# joint_board_boosterpack_hall_effect_enco.net
KiCad netlist of a schematic drawn in Altium Designer
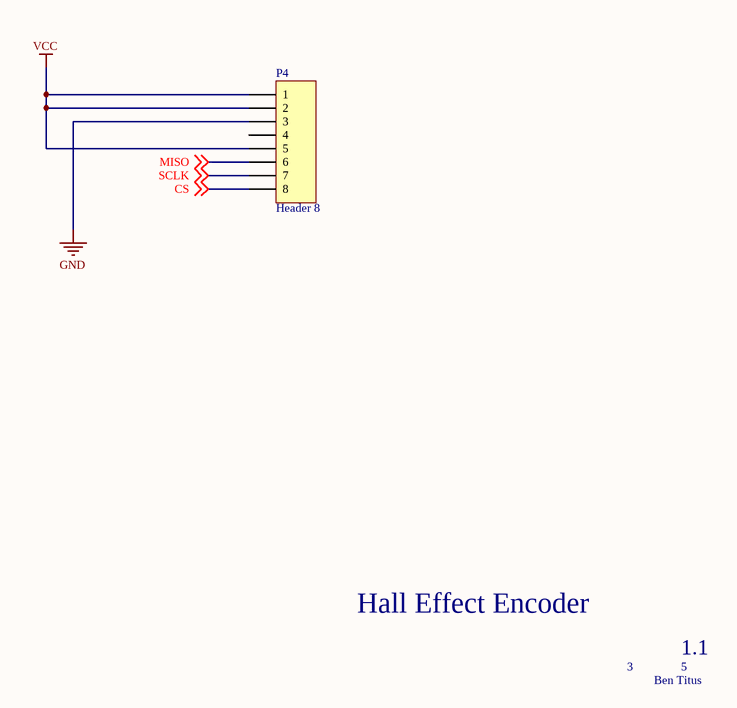
[diagram p0: joint_board_boosterpack_hall_effect_encoder.SchDoc]

(export (version "E")
  (design (tool "Eeschema 10.0.6"))
  (components
    (comp (ref "P4")
      (value "Header 8")
      (footprint "HDR1X8")
      (description "Header, 8-Pin")
      (fields (field (name "PUBLISHER") "Altium Limited"))
      (libsource (lib "Miscellaneous Connectors") (part "Header 8"))
    )
  )
  (nets
    (net (code "1") (name "CS") (class "Default")
      (node (ref "P4") (pin "8") (pinfunction "8_8") (pintype "passive"))
    )
    (net (code "2") (name "GND") (class "Default")
      (node (ref "P4") (pin "3") (pinfunction "3_3") (pintype "passive"))
    )
    (net (code "3") (name "MISO") (class "Default")
      (node (ref "P4") (pin "6") (pinfunction "6_6") (pintype "passive"))
    )
    (net (code "4") (name "SCLK") (class "Default")
      (node (ref "P4") (pin "7") (pinfunction "7_7") (pintype "passive"))
    )
    (net (code "5") (name "VCC") (class "Default")
      (node (ref "P4") (pin "1") (pinfunction "1_1") (pintype "passive"))
      (node (ref "P4") (pin "2") (pinfunction "2_2") (pintype "passive"))
      (node (ref "P4") (pin "5") (pinfunction "5_5") (pintype "passive"))
    )
    (net (code "6") (name "unconnected-(P4-Pad4)") (class "Default")
      (node (ref "P4") (pin "4") (pinfunction "4_4") (pintype "passive"))
    )
  )
)
